# SH-C30G-V1_5.net
KiCad netlist of a schematic drawn in Altium Designer
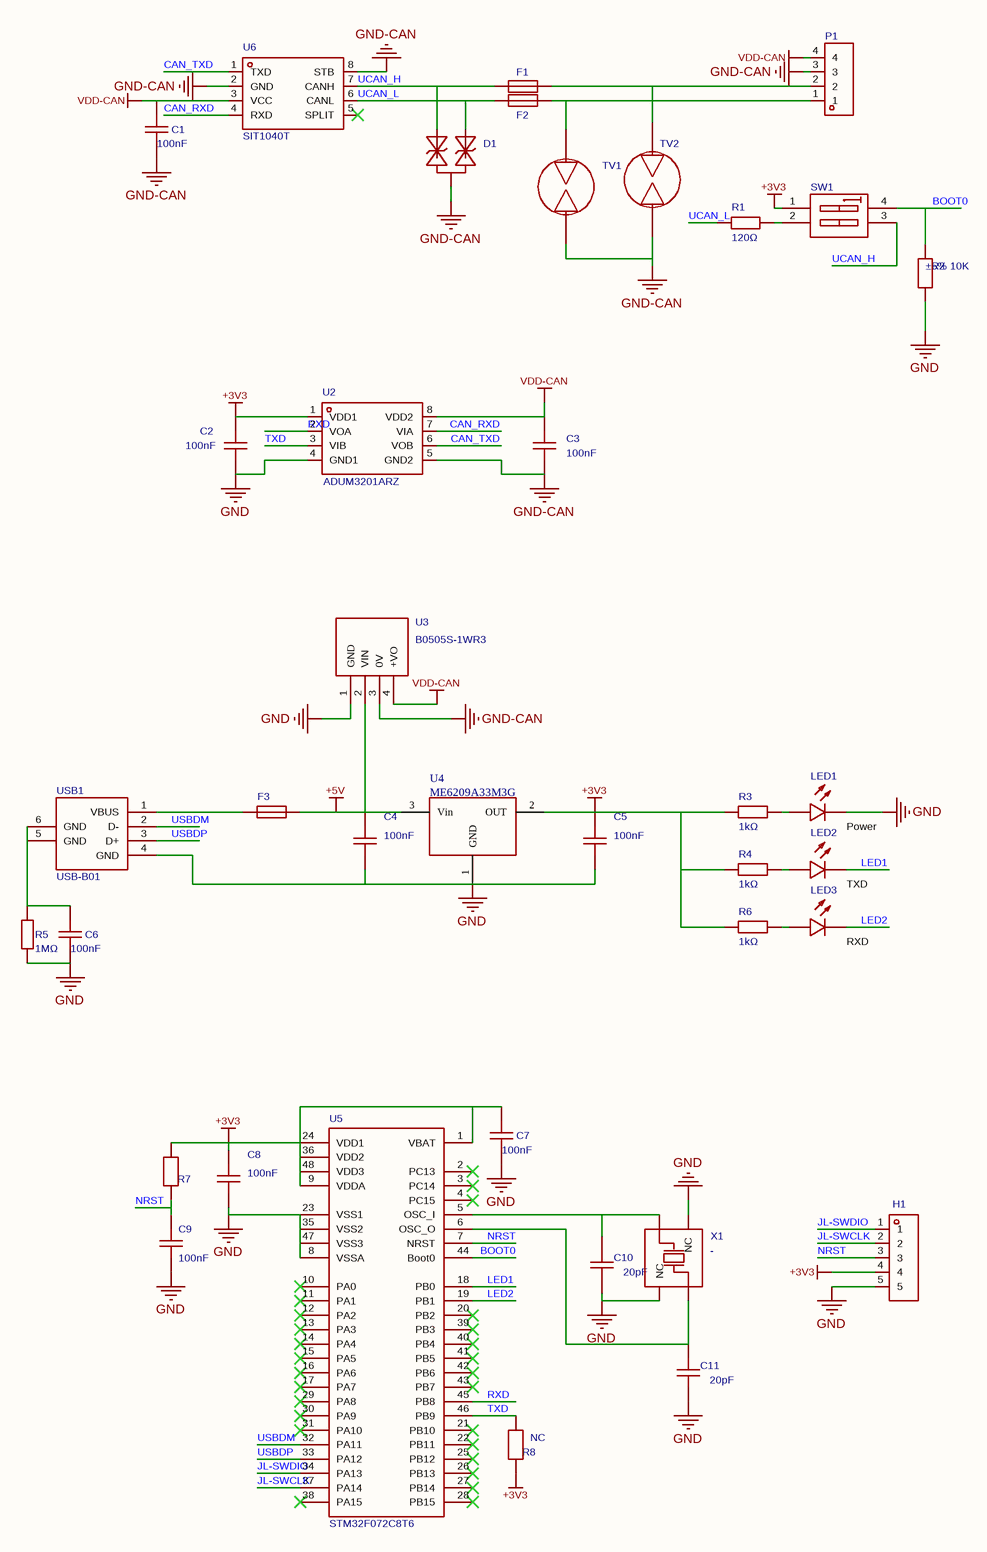
[diagram p0: SH-C30G-V1.5.SchDoc]

(export (version "E")
  (design (tool "Eeschema 10.0.6"))
  (components
    (comp (ref "C1")
      (value "100nF")
      (footprint "C0402")
      (description "Capacitance:100nF;Tolerance:±10%;Rated Voltage:50V;Temp. Coefficient:X7R;")
      (fields (field (name "MANUFACTURER") "IHHEC") (field (name "MANUFACTURERPART") "C0402X104K050T"))
      (libsource (lib "altium-import") (part "root_1_C0402X104K050T_"))
    )
    (comp (ref "C2")
      (value "100nF")
      (footprint "C0402")
      (description "Capacitance:100nF;Tolerance:±10%;Rated Voltage:50V;Temp. Coefficient:X7R;")
      (fields (field (name "MANUFACTURER") "IHHEC") (field (name "MANUFACTURERPART") "C0402X104K050T"))
      (libsource (lib "altium-import") (part "root_1_C0402X104K050T_"))
    )
    (comp (ref "C3")
      (value "100nF")
      (footprint "C0402")
      (description "Capacitance:100nF;Tolerance:±10%;Rated Voltage:50V;Temp. Coefficient:X7R;")
      (fields (field (name "MANUFACTURER") "IHHEC") (field (name "MANUFACTURERPART") "C0402X104K050T"))
      (libsource (lib "altium-import") (part "root_1_mirrored_C0402X104K050T_"))
    )
    (comp (ref "C4")
      (value "100nF")
      (footprint "C0402")
      (description "Capacitance:100nF;Tolerance:±10%;Rated Voltage:50V;Temp. Coefficient:X7R;")
      (fields (field (name "MANUFACTURER") "IHHEC") (field (name "MANUFACTURERPART") "C0402X104K050T"))
      (libsource (lib "altium-import") (part "root_1_C0402X104K050T_"))
    )
    (comp (ref "C5")
      (value "100nF")
      (footprint "C0402")
      (description "Capacitance:100nF;Tolerance:±10%;Rated Voltage:50V;Temp. Coefficient:X7R;")
      (fields (field (name "MANUFACTURER") "IHHEC") (field (name "MANUFACTURERPART") "C0402X104K050T"))
      (libsource (lib "altium-import") (part "root_1_C0402X104K050T_"))
    )
    (comp (ref "C6")
      (value "100nF")
      (footprint "C0402")
      (description "Capacitance:100nF;Tolerance:±10%;Rated Voltage:50V;Temp. Coefficient:X7R;")
      (fields (field (name "MANUFACTURER") "IHHEC") (field (name "MANUFACTURERPART") "C0402X104K050T"))
      (libsource (lib "altium-import") (part "root_1_C0402X104K050T_"))
    )
    (comp (ref "C7")
      (value "100nF")
      (footprint "C0402")
      (description "Capacitance:100nF;Tolerance:±10%;Rated Voltage:50V;Temp. Coefficient:X7R;")
      (fields (field (name "MANUFACTURER") "IHHEC") (field (name "MANUFACTURERPART") "C0402X104K050T"))
      (libsource (lib "altium-import") (part "root_1_C0402X104K050T_"))
    )
    (comp (ref "C8")
      (value "100nF")
      (footprint "C0402")
      (description "Capacitance:100nF;Tolerance:±10%;Rated Voltage:50V;Temp. Coefficient:X7R;")
      (fields (field (name "MANUFACTURER") "IHHEC") (field (name "MANUFACTURERPART") "C0402X104K050T"))
      (libsource (lib "altium-import") (part "root_1_C0402X104K050T_"))
    )
    (comp (ref "C9")
      (value "100nF")
      (footprint "C0402")
      (description "Capacitance:100nF;Tolerance:±10%;Rated Voltage:50V;Temp. Coefficient:X7R;")
      (fields (field (name "MANUFACTURER") "IHHEC") (field (name "MANUFACTURERPART") "C0402X104K050T"))
      (libsource (lib "altium-import") (part "root_1_C0402X104K050T_"))
    )
    (comp (ref "C10")
      (value "20pF")
      (footprint "C0402")
      (description "Capacitance:20pF;Tolerance:±5%;Rated Voltage:50V;Temp. Coefficient:C0G;")
      (fields (field (name "MANUFACTURER") "muRata") (field (name "MANUFACTURERPART") "GRM1555C1H200JA01D"))
      (libsource (lib "altium-import") (part "root_3_GRM1555C1H200JA01D_"))
    )
    (comp (ref "C11")
      (value "20pF")
      (footprint "C0402")
      (description "Capacitance:20pF;Tolerance:±5%;Rated Voltage:50V;Temp. Coefficient:C0G;")
      (fields (field (name "MANUFACTURER") "muRata") (field (name "MANUFACTURERPART") "GRM1555C1H200JA01D"))
      (libsource (lib "altium-import") (part "root_1_GRM1555C1H200JA01D_"))
    )
    (comp (ref "D1")
      (value "~")
      (footprint "SOT-23-3_L2.9-W1.3-P1.90-LS2.4-BR")
      (fields (field (name "MANUFACTURER") "TECH PUBLIC") (field (name "MANUFACTURERPART") "TPPESD12VL2BT"))
      (libsource (lib "altium-import") (part "root_2_TPPESD12VL2BT_"))
    )
    (comp (ref "F1")
      (value "SMD1206B020TF/24")
      (footprint "F1206_1")
      (description "Max Voltage:24V;Max Current:100A;Hold Current:200mA;Trip Current:420mA;Max Trip Time:100ms;")
      (fields (field (name "MANUFACTURER") "Brightking"))
      (libsource (lib "altium-import") (part "root_0_SMD1206B020TF/24_"))
    )
    (comp (ref "F2")
      (value "SMD1206B020TF/24")
      (footprint "F1206_1")
      (description "Max Voltage:24V;Max Current:100A;Hold Current:200mA;Trip Current:420mA;Max Trip Time:100ms;")
      (fields (field (name "MANUFACTURER") "Brightking"))
      (libsource (lib "altium-import") (part "root_0_SMD1206B020TF/24_"))
    )
    (comp (ref "F3")
      (value "SMD0805B050TF")
      (footprint "F0805_2")
      (description "Max Voltage:6V;Max Current:100A;Hold Current:500mA;Trip Current:1A;Max Trip Time:100ms;")
      (fields (field (name "MANUFACTURER") "Brightking"))
      (libsource (lib "altium-import") (part "root_0_SMD0805B050TF_"))
    )
    (comp (ref "H1")
      (value "~")
      (footprint "HDR-TH_5P-P2.54-V-M")
      (fields (field (name "MANUFACTURER") "XFCN") (field (name "MANUFACTURERPART") "PZ254V-11-05P"))
      (libsource (lib "altium-import") (part "root_0_PZ254V-11-05P_"))
    )
    (comp (ref "LED1")
      (value "~")
      (footprint "LED0603-RD_RED_1")
      (description "Emitted Color:Red;")
      (fields (field (name "MANUFACTURER") "NationStar") (field (name "MANUFACTURERPART") "NCD0603R1"))
      (libsource (lib "altium-import") (part "root_0_mirrored_NCD0603R1_C84263_"))
    )
    (comp (ref "LED2")
      (value "~")
      (footprint "LED0603-RD")
      (description "Emitted Color:Emerald Green;")
      (fields (field (name "MANUFACTURER") "NationStar") (field (name "MANUFACTURERPART") "NCD0603G1"))
      (libsource (lib "altium-import") (part "root_0_NCD0603G1_"))
    )
    (comp (ref "LED3")
      (value "~")
      (footprint "LED0603-RD")
      (description "Emitted Color:Emerald Green;")
      (fields (field (name "MANUFACTURER") "NationStar") (field (name "MANUFACTURERPART") "NCD0603G1"))
      (libsource (lib "altium-import") (part "root_0_NCD0603G1_"))
    )
    (comp (ref "P1")
      (value "WJ128V-5.0-4P")
      (footprint "CONN-TH_4P-P5.00_WJ128V-4P-5.0-14-00A")
      (fields (field (name "MANUFACTURER") "KANGNEX"))
      (libsource (lib "altium-import") (part "root_2_mirrored_WJ128V-5.0-4P_"))
    )
    (comp (ref "R1")
      (value "120Ω")
      (footprint "R0805")
      (fields
        (field (name "MANUFACTURER") "UNI-ROYAL")
        (field (name "MANUFACTURERPART") "TC0525F1200T5E")
        (field (name "TOLERANCE") "±1%")
      )
      (libsource (lib "altium-import") (part "root_0_TC0525F1200T5E_"))
    )
    (comp (ref "R2")
      (value "~")
      (footprint "R0402")
      (fields
        (field (name "LCSC PART NAME") "±5% 10K")
        (field (name "MANUFACTURER") "VO")
        (field (name "MANUFACTURERPART") "SCR0402J10K")
      )
      (libsource (lib "altium-import") (part "root_1_SCR0402J10K_"))
    )
    (comp (ref "R3")
      (value "1kΩ")
      (footprint "R0402")
      (fields
        (field (name "MANUFACTURER") "YAGEO")
        (field (name "MANUFACTURERPART") "RC0402JR-071KL")
        (field (name "TOLERANCE") "±5%")
      )
      (libsource (lib "altium-import") (part "root_0_RC0402JR-071KL_"))
    )
    (comp (ref "R4")
      (value "1kΩ")
      (footprint "R0402")
      (fields
        (field (name "MANUFACTURER") "YAGEO")
        (field (name "MANUFACTURERPART") "RC0402JR-071KL")
        (field (name "TOLERANCE") "±5%")
      )
      (libsource (lib "altium-import") (part "root_0_RC0402JR-071KL_"))
    )
    (comp (ref "R5")
      (value "1MΩ")
      (footprint "R0603")
      (fields
        (field (name "MANUFACTURER") "UNI-ROYAL")
        (field (name "MANUFACTURERPART") "0603WAJ0105T5E")
        (field (name "TOLERANCE") "±5%")
      )
      (libsource (lib "altium-import") (part "root_1_0603WAJ0105T5E_"))
    )
    (comp (ref "R6")
      (value "1kΩ")
      (footprint "R0402")
      (fields
        (field (name "MANUFACTURER") "YAGEO")
        (field (name "MANUFACTURERPART") "RC0402JR-071KL")
        (field (name "TOLERANCE") "±5%")
      )
      (libsource (lib "altium-import") (part "root_0_RC0402JR-071KL_"))
    )
    (comp (ref "R7")
      (value "~")
      (footprint "R0402")
      (fields (field (name "MANUFACTURER") "VO") (field (name "MANUFACTURERPART") "SCR0402J10K"))
      (libsource (lib "altium-import") (part "root_1_SCR0402J10K_"))
    )
    (comp (ref "R8")
      (value "NC")
      (footprint "R0402")
      (fields (field (name "MANUFACTURER") "VO") (field (name "MANUFACTURERPART") "SCR0402J10K"))
      (libsource (lib "altium-import") (part "root_1_SCR0402J10K_"))
    )
    (comp (ref "SW1")
      (value "DP-02RP")
      (footprint "SW-TH_DP-02XP")
      (fields (field (name "MANUFACTURER") "HRO"))
      (libsource (lib "altium-import") (part "root_0_DP-02RP_"))
    )
    (comp (ref "TV1")
      (value "~")
      (footprint "DIO-DT-SMD_L4.5-W3.2")
      (fields
        (field (name "MANUFACTURER") "RUILON")
        (field (name "MANUFACTURERPART") "SMD4532-090NF")
        (field (name "TOLERANCE") "±30%")
      )
      (libsource (lib "altium-import") (part "root_0_SMD4532-090NF_"))
    )
    (comp (ref "TV2")
      (value "~")
      (footprint "DIO-DT-SMD_L4.5-W3.2")
      (fields
        (field (name "MANUFACTURER") "RUILON")
        (field (name "MANUFACTURERPART") "SMD4532-090NF")
        (field (name "TOLERANCE") "±30%")
      )
      (libsource (lib "altium-import") (part "root_0_SMD4532-090NF_"))
    )
    (comp (ref "U2")
      (value "ADUM3201ARZ")
      (footprint "SOIC-8_L4.9-W3.9-P1.27-LS6.0-BL")
      (description "Application:-;Isolation Technology:-;Voltage Isolation:-;")
      (fields (field (name "MANUFACTURER PART") "ADUM3201ARZ") (field (name "MANUFACTURER") "ADI / LINEAR"))
      (libsource (lib "altium-import") (part "root_0_ADUM3201ARZ_"))
    )
    (comp (ref "U3")
      (value "B0505S-1WR3_C131038")
      (footprint "PWRM-TH_B0503S-1WR2")
      (fields (field (name "MANUFACTURER PART") "B0505S-1WR3") (field (name "MANUFACTURER") "MORNSUN"))
      (libsource (lib "altium-import") (part "root_1_B0505S-1WR3_C131038_"))
    )
    (comp (ref "U4")
      (value "ME6209A33M3G")
      (footprint "SOT-23(SOT-23-3)")
      (libsource (lib "altium-import") (part "root_0_ME6209A33M3G_"))
    )
    (comp (ref "U5")
      (value "~")
      (footprint "LQFP-48_L7.0-W7.0-P0.50-LS9.0-BL")
      (description "CPU Core:ARM® Cortex®-M0;Supply Voltage:1.65V ~ 3.6V;")
      (fields (field (name "MANUFACTURER PART") "STM32F072C8T6") (field (name "MANUFACTURER") "ST"))
      (libsource (lib "altium-import") (part "root_0_STM32F072C8T6_"))
    )
    (comp (ref "U6")
      (value "SIT1040T")
      (footprint "SO-8_L4.9-W3.9-P1.27-LS5.9-BL")
      (description "Type:Transceiver;Data Rate:1Mbps;Supply Voltage (Vcc):4.5V~5.5V;")
      (fields (field (name "MANUFACTURER PART") "SIT1040T") (field (name "MANUFACTURER") "SIT"))
      (libsource (lib "altium-import") (part "root_0_SIT1040T_"))
    )
    (comp (ref "USB1")
      (value "~")
      (footprint "USB-B-TH_USB-B01")
      (fields (field (name "MANUFACTURER PART") "USB-B01") (field (name "MANUFACTURER") "SOFNG"))
      (libsource (lib "altium-import") (part "root_0_mirrored_USB-B01_"))
    )
    (comp (ref "X1")
      (value "-")
      (footprint "CRYSTAL-SMD_4P-L3.2-W2.5-BL")
      (description "Crystal Type:-;Frequency:-;Load Capacitance:-;Operating Temp.:-;")
      (fields (field (name "MANUFACTURER") "TXC") (field (name "MANUFACTURERPART") "7V24000005"))
      (libsource (lib "altium-import") (part "root_3_7V24000005_"))
    )
  )
  (nets
    (net (code "1") (name "+3V3") (class "Default")
      (node (ref "C2") (pin "2") (pinfunction "2_2") (pintype "passive"))
      (node (ref "C5") (pin "2") (pinfunction "2_2") (pintype "passive"))
      (node (ref "C7") (pin "2") (pinfunction "2_2") (pintype "passive"))
      (node (ref "C8") (pin "2") (pinfunction "2_2") (pintype "passive"))
      (node (ref "H1") (pin "4") (pinfunction "4_4") (pintype "passive"))
      (node (ref "R3") (pin "1") (pinfunction "1_1") (pintype "passive"))
      (node (ref "R4") (pin "1") (pinfunction "1_1") (pintype "passive"))
      (node (ref "R6") (pin "1") (pinfunction "1_1") (pintype "passive"))
      (node (ref "R7") (pin "2") (pinfunction "2_2") (pintype "passive"))
      (node (ref "R8") (pin "1") (pinfunction "1_1") (pintype "passive"))
      (node (ref "SW1") (pin "1") (pinfunction "A1_1") (pintype "passive"))
      (node (ref "U2") (pin "1") (pinfunction "VDD1_1") (pintype "passive"))
      (node (ref "U4") (pin "2") (pinfunction "OUT_2") (pintype "passive"))
      (node (ref "U5") (pin "1") (pinfunction "VBAT_1") (pintype "passive"))
      (node (ref "U5") (pin "24") (pinfunction "VDD1_24") (pintype "passive"))
      (node (ref "U5") (pin "36") (pinfunction "VDD2_36") (pintype "passive"))
      (node (ref "U5") (pin "48") (pinfunction "VDD3_48") (pintype "passive"))
      (node (ref "U5") (pin "9") (pinfunction "VDDA_9") (pintype "passive"))
    )
    (net (code "2") (name "+5V") (class "Default")
      (node (ref "C4") (pin "2") (pinfunction "2_2") (pintype "passive"))
      (node (ref "F3") (pin "2") (pinfunction "2_2") (pintype "passive"))
      (node (ref "U3") (pin "2") (pinfunction "VIN_2") (pintype "passive"))
      (node (ref "U4") (pin "3") (pinfunction "Vin_3") (pintype "passive"))
    )
    (net (code "3") (name "/BOOT0") (class "Default")
      (node (ref "R2") (pin "2") (pinfunction "2_2") (pintype "passive"))
      (node (ref "SW1") (pin "4") (pinfunction "4_4") (pintype "passive"))
      (node (ref "U5") (pin "44") (pinfunction "Boot0_44") (pintype "passive"))
    )
    (net (code "4") (name "/CAN_RXD") (class "Default")
      (node (ref "U2") (pin "7") (pinfunction "VIA_7") (pintype "passive"))
      (node (ref "U6") (pin "4") (pinfunction "RXD_4") (pintype "passive"))
    )
    (net (code "5") (name "/CAN_TXD") (class "Default")
      (node (ref "U2") (pin "6") (pinfunction "VOB_6") (pintype "passive"))
      (node (ref "U6") (pin "1") (pinfunction "TXD_1") (pintype "passive"))
    )
    (net (code "6") (name "/JL-SWCLK") (class "Default")
      (node (ref "H1") (pin "2") (pinfunction "2_2") (pintype "passive"))
      (node (ref "U5") (pin "37") (pinfunction "PA14_37") (pintype "passive"))
    )
    (net (code "7") (name "/JL-SWDIO") (class "Default")
      (node (ref "H1") (pin "1") (pinfunction "1_1") (pintype "passive"))
      (node (ref "U5") (pin "34") (pinfunction "PA13_34") (pintype "passive"))
    )
    (net (code "8") (name "/LED1") (class "Default")
      (node (ref "LED2") (pin "1") (pinfunction "K_1") (pintype "passive"))
      (node (ref "U5") (pin "18") (pinfunction "PB0_18") (pintype "passive"))
    )
    (net (code "9") (name "/LED2") (class "Default")
      (node (ref "LED3") (pin "1") (pinfunction "K_1") (pintype "passive"))
      (node (ref "U5") (pin "19") (pinfunction "PB1_19") (pintype "passive"))
    )
    (net (code "10") (name "/NRST") (class "Default")
      (node (ref "C9") (pin "2") (pinfunction "2_2") (pintype "passive"))
      (node (ref "H1") (pin "3") (pinfunction "3_3") (pintype "passive"))
      (node (ref "R7") (pin "1") (pinfunction "1_1") (pintype "passive"))
      (node (ref "U5") (pin "7") (pinfunction "NRST_7") (pintype "passive"))
    )
    (net (code "11") (name "/RXD") (class "Default")
      (node (ref "U2") (pin "2") (pinfunction "VOA_2") (pintype "passive"))
      (node (ref "U5") (pin "45") (pinfunction "PB8_45") (pintype "passive"))
    )
    (net (code "12") (name "/TXD") (class "Default")
      (node (ref "R8") (pin "2") (pinfunction "2_2") (pintype "passive"))
      (node (ref "U2") (pin "3") (pinfunction "VIB_3") (pintype "passive"))
      (node (ref "U5") (pin "46") (pinfunction "PB9_46") (pintype "passive"))
    )
    (net (code "13") (name "/UCAN_H") (class "Default")
      (node (ref "D1") (pin "2") (pinfunction "2_2") (pintype "passive"))
      (node (ref "F1") (pin "1") (pinfunction "1_1") (pintype "passive"))
      (node (ref "SW1") (pin "3") (pinfunction "3_3") (pintype "passive"))
      (node (ref "U6") (pin "7") (pinfunction "CANH_7") (pintype "passive"))
    )
    (net (code "14") (name "/UCAN_L") (class "Default")
      (node (ref "D1") (pin "1") (pinfunction "1_1") (pintype "passive"))
      (node (ref "F2") (pin "1") (pinfunction "1_1") (pintype "passive"))
      (node (ref "R1") (pin "1") (pinfunction "1_1") (pintype "passive"))
      (node (ref "U6") (pin "6") (pinfunction "CANL_6") (pintype "passive"))
    )
    (net (code "15") (name "/USBDM") (class "Default")
      (node (ref "U5") (pin "32") (pinfunction "PA11_32") (pintype "passive"))
      (node (ref "USB1") (pin "2") (pinfunction "D-_2") (pintype "passive"))
    )
    (net (code "16") (name "/USBDP") (class "Default")
      (node (ref "U5") (pin "33") (pinfunction "PA12_33") (pintype "passive"))
      (node (ref "USB1") (pin "3") (pinfunction "D+_3") (pintype "passive"))
    )
    (net (code "17") (name "GND") (class "Default")
      (node (ref "C10") (pin "2") (pinfunction "2_2") (pintype "passive"))
      (node (ref "C11") (pin "1") (pinfunction "1_1") (pintype "passive"))
      (node (ref "C2") (pin "1") (pinfunction "1_1") (pintype "passive"))
      (node (ref "C4") (pin "1") (pinfunction "1_1") (pintype "passive"))
      (node (ref "C5") (pin "1") (pinfunction "1_1") (pintype "passive"))
      (node (ref "C6") (pin "1") (pinfunction "1_1") (pintype "passive"))
      (node (ref "C7") (pin "1") (pinfunction "1_1") (pintype "passive"))
      (node (ref "C8") (pin "1") (pinfunction "1_1") (pintype "passive"))
      (node (ref "C9") (pin "1") (pinfunction "1_1") (pintype "passive"))
      (node (ref "H1") (pin "5") (pinfunction "5_5") (pintype "passive"))
      (node (ref "LED1") (pin "1") (pinfunction "K_1") (pintype "passive"))
      (node (ref "R2") (pin "1") (pinfunction "1_1") (pintype "passive"))
      (node (ref "R5") (pin "1") (pinfunction "1_1") (pintype "passive"))
      (node (ref "U2") (pin "4") (pinfunction "GND1_4") (pintype "passive"))
      (node (ref "U3") (pin "1") (pinfunction "GND_1") (pintype "passive"))
      (node (ref "U4") (pin "1") (pinfunction "GND_1") (pintype "passive"))
      (node (ref "U5") (pin "23") (pinfunction "VSS1_23") (pintype "passive"))
      (node (ref "U5") (pin "35") (pinfunction "VSS2_35") (pintype "passive"))
      (node (ref "U5") (pin "47") (pinfunction "VSS3_47") (pintype "passive"))
      (node (ref "U5") (pin "8") (pinfunction "VSSA_8") (pintype "passive"))
      (node (ref "USB1") (pin "4") (pinfunction "GND_4") (pintype "passive"))
      (node (ref "X1") (pin "2") (pinfunction "NC_2") (pintype "passive"))
      (node (ref "X1") (pin "4") (pinfunction "NC_4") (pintype "passive"))
    )
    (net (code "18") (name "GND-CAN") (class "Default")
      (node (ref "C1") (pin "1") (pinfunction "1_1") (pintype "passive"))
      (node (ref "C3") (pin "1") (pinfunction "1_1") (pintype "passive"))
      (node (ref "D1") (pin "3") (pinfunction "3_3") (pintype "passive"))
      (node (ref "P1") (pin "3") (pinfunction "3_3") (pintype "passive"))
      (node (ref "TV1") (pin "2") (pinfunction "2_2") (pintype "passive"))
      (node (ref "TV2") (pin "2") (pinfunction "2_2") (pintype "passive"))
      (node (ref "U2") (pin "5") (pinfunction "GND2_5") (pintype "passive"))
      (node (ref "U3") (pin "3") (pinfunction "0V_3") (pintype "passive"))
      (node (ref "U6") (pin "2") (pinfunction "GND_2") (pintype "passive"))
      (node (ref "U6") (pin "8") (pinfunction "STB_8") (pintype "passive"))
    )
    (net (code "19") (name "Net-(C6-Pad2)") (class "Default")
      (node (ref "C6") (pin "2") (pinfunction "2_2") (pintype "passive"))
      (node (ref "R5") (pin "2") (pinfunction "2_2") (pintype "passive"))
      (node (ref "USB1") (pin "5") (pinfunction "GND_5") (pintype "passive"))
      (node (ref "USB1") (pin "6") (pinfunction "GND_6") (pintype "passive"))
    )
    (net (code "20") (name "Net-(F1-Pad2)") (class "Default")
      (node (ref "F1") (pin "2") (pinfunction "2_2") (pintype "passive"))
      (node (ref "P1") (pin "2") (pinfunction "2_2") (pintype "passive"))
      (node (ref "TV2") (pin "1") (pinfunction "1_1") (pintype "passive"))
    )
    (net (code "21") (name "Net-(F2-Pad2)") (class "Default")
      (node (ref "F2") (pin "2") (pinfunction "2_2") (pintype "passive"))
      (node (ref "P1") (pin "1") (pinfunction "1_1") (pintype "passive"))
      (node (ref "TV1") (pin "1") (pinfunction "1_1") (pintype "passive"))
    )
    (net (code "22") (name "Net-(LED1-A)") (class "Default")
      (node (ref "LED1") (pin "2") (pinfunction "A_2") (pintype "passive"))
      (node (ref "R3") (pin "2") (pinfunction "2_2") (pintype "passive"))
    )
    (net (code "23") (name "Net-(LED2-A)") (class "Default")
      (node (ref "LED2") (pin "2") (pinfunction "A_2") (pintype "passive"))
      (node (ref "R4") (pin "2") (pinfunction "2_2") (pintype "passive"))
    )
    (net (code "24") (name "Net-(LED3-A)") (class "Default")
      (node (ref "LED3") (pin "2") (pinfunction "A_2") (pintype "passive"))
      (node (ref "R6") (pin "2") (pinfunction "2_2") (pintype "passive"))
    )
    (net (code "25") (name "Net-(SW1-A2)") (class "Default")
      (node (ref "R1") (pin "2") (pinfunction "2_2") (pintype "passive"))
      (node (ref "SW1") (pin "2") (pinfunction "A2_2") (pintype "passive"))
    )
    (net (code "26") (name "Net-(U5-OSC_I)") (class "Default")
      (node (ref "C10") (pin "1") (pinfunction "1_1") (pintype "passive"))
      (node (ref "U5") (pin "5") (pinfunction "OSC_I_5") (pintype "passive"))
      (node (ref "X1") (pin "1") (pinfunction "OSC1_1") (pintype "passive"))
    )
    (net (code "27") (name "Net-(U5-OSC_O)") (class "Default")
      (node (ref "C11") (pin "2") (pinfunction "2_2") (pintype "passive"))
      (node (ref "U5") (pin "6") (pinfunction "OSC_O_6") (pintype "passive"))
      (node (ref "X1") (pin "3") (pinfunction "OSC2_3") (pintype "passive"))
    )
    (net (code "28") (name "Net-(USB1-VBUS)") (class "Default")
      (node (ref "F3") (pin "1") (pinfunction "1_1") (pintype "passive"))
      (node (ref "USB1") (pin "1") (pinfunction "VBUS_1") (pintype "passive"))
    )
    (net (code "29") (name "VDD-CAN") (class "Default")
      (node (ref "C1") (pin "2") (pinfunction "2_2") (pintype "passive"))
      (node (ref "C3") (pin "2") (pinfunction "2_2") (pintype "passive"))
      (node (ref "P1") (pin "4") (pinfunction "4_4") (pintype "passive"))
      (node (ref "U2") (pin "8") (pinfunction "VDD2_8") (pintype "passive"))
      (node (ref "U3") (pin "4") (pinfunction "+VO_4") (pintype "passive"))
      (node (ref "U6") (pin "3") (pinfunction "VCC_3") (pintype "passive"))
    )
    (net (code "30") (name "unconnected-(U5-PA0-Pad10)") (class "Default")
      (node (ref "U5") (pin "10") (pinfunction "PA0_10") (pintype "passive+no_connect"))
    )
    (net (code "31") (name "unconnected-(U5-PA1-Pad11)") (class "Default")
      (node (ref "U5") (pin "11") (pinfunction "PA1_11") (pintype "passive+no_connect"))
    )
    (net (code "32") (name "unconnected-(U5-PA2-Pad12)") (class "Default")
      (node (ref "U5") (pin "12") (pinfunction "PA2_12") (pintype "passive+no_connect"))
    )
    (net (code "33") (name "unconnected-(U5-PA3-Pad13)") (class "Default")
      (node (ref "U5") (pin "13") (pinfunction "PA3_13") (pintype "passive+no_connect"))
    )
    (net (code "34") (name "unconnected-(U5-PA4-Pad14)") (class "Default")
      (node (ref "U5") (pin "14") (pinfunction "PA4_14") (pintype "passive+no_connect"))
    )
    (net (code "35") (name "unconnected-(U5-PA5-Pad15)") (class "Default")
      (node (ref "U5") (pin "15") (pinfunction "PA5_15") (pintype "passive+no_connect"))
    )
    (net (code "36") (name "unconnected-(U5-PA6-Pad16)") (class "Default")
      (node (ref "U5") (pin "16") (pinfunction "PA6_16") (pintype "passive+no_connect"))
    )
    (net (code "37") (name "unconnected-(U5-PA7-Pad17)") (class "Default")
      (node (ref "U5") (pin "17") (pinfunction "PA7_17") (pintype "passive+no_connect"))
    )
    (net (code "38") (name "unconnected-(U5-PA8-Pad29)") (class "Default")
      (node (ref "U5") (pin "29") (pinfunction "PA8_29") (pintype "passive+no_connect"))
    )
    (net (code "39") (name "unconnected-(U5-PA9-Pad30)") (class "Default")
      (node (ref "U5") (pin "30") (pinfunction "PA9_30") (pintype "passive+no_connect"))
    )
    (net (code "40") (name "unconnected-(U5-PA10-Pad31)") (class "Default")
      (node (ref "U5") (pin "31") (pinfunction "PA10_31") (pintype "passive+no_connect"))
    )
    (net (code "41") (name "unconnected-(U5-PA15-Pad38)") (class "Default")
      (node (ref "U5") (pin "38") (pinfunction "PA15_38") (pintype "passive+no_connect"))
    )
    (net (code "42") (name "unconnected-(U5-PB2-Pad20)") (class "Default")
      (node (ref "U5") (pin "20") (pinfunction "PB2_20") (pintype "passive+no_connect"))
    )
    (net (code "43") (name "unconnected-(U5-PB3-Pad39)") (class "Default")
      (node (ref "U5") (pin "39") (pinfunction "PB3_39") (pintype "passive+no_connect"))
    )
    (net (code "44") (name "unconnected-(U5-PB4-Pad40)") (class "Default")
      (node (ref "U5") (pin "40") (pinfunction "PB4_40") (pintype "passive+no_connect"))
    )
    (net (code "45") (name "unconnected-(U5-PB5-Pad41)") (class "Default")
      (node (ref "U5") (pin "41") (pinfunction "PB5_41") (pintype "passive+no_connect"))
    )
    (net (code "46") (name "unconnected-(U5-PB6-Pad42)") (class "Default")
      (node (ref "U5") (pin "42") (pinfunction "PB6_42") (pintype "passive+no_connect"))
    )
    (net (code "47") (name "unconnected-(U5-PB7-Pad43)") (class "Default")
      (node (ref "U5") (pin "43") (pinfunction "PB7_43") (pintype "passive+no_connect"))
    )
    (net (code "48") (name "unconnected-(U5-PB10-Pad21)") (class "Default")
      (node (ref "U5") (pin "21") (pinfunction "PB10_21") (pintype "passive+no_connect"))
    )
    (net (code "49") (name "unconnected-(U5-PB11-Pad22)") (class "Default")
      (node (ref "U5") (pin "22") (pinfunction "PB11_22") (pintype "passive+no_connect"))
    )
    (net (code "50") (name "unconnected-(U5-PB12-Pad25)") (class "Default")
      (node (ref "U5") (pin "25") (pinfunction "PB12_25") (pintype "passive+no_connect"))
    )
    (net (code "51") (name "unconnected-(U5-PB13-Pad26)") (class "Default")
      (node (ref "U5") (pin "26") (pinfunction "PB13_26") (pintype "passive+no_connect"))
    )
    (net (code "52") (name "unconnected-(U5-PB14-Pad27)") (class "Default")
      (node (ref "U5") (pin "27") (pinfunction "PB14_27") (pintype "passive+no_connect"))
    )
    (net (code "53") (name "unconnected-(U5-PB15-Pad28)") (class "Default")
      (node (ref "U5") (pin "28") (pinfunction "PB15_28") (pintype "passive+no_connect"))
    )
    (net (code "54") (name "unconnected-(U5-PC13-Pad2)") (class "Default")
      (node (ref "U5") (pin "2") (pinfunction "PC13_2") (pintype "passive+no_connect"))
    )
    (net (code "55") (name "unconnected-(U5-PC14-Pad3)") (class "Default")
      (node (ref "U5") (pin "3") (pinfunction "PC14_3") (pintype "passive+no_connect"))
    )
    (net (code "56") (name "unconnected-(U5-PC15-Pad4)") (class "Default")
      (node (ref "U5") (pin "4") (pinfunction "PC15_4") (pintype "passive+no_connect"))
    )
    (net (code "57") (name "unconnected-(U6-SPLIT-Pad5)") (class "Default")
      (node (ref "U6") (pin "5") (pinfunction "SPLIT_5") (pintype "passive+no_connect"))
    )
  )
)
